# POWER.net
KiCad netlist of a schematic drawn in Altium Designer
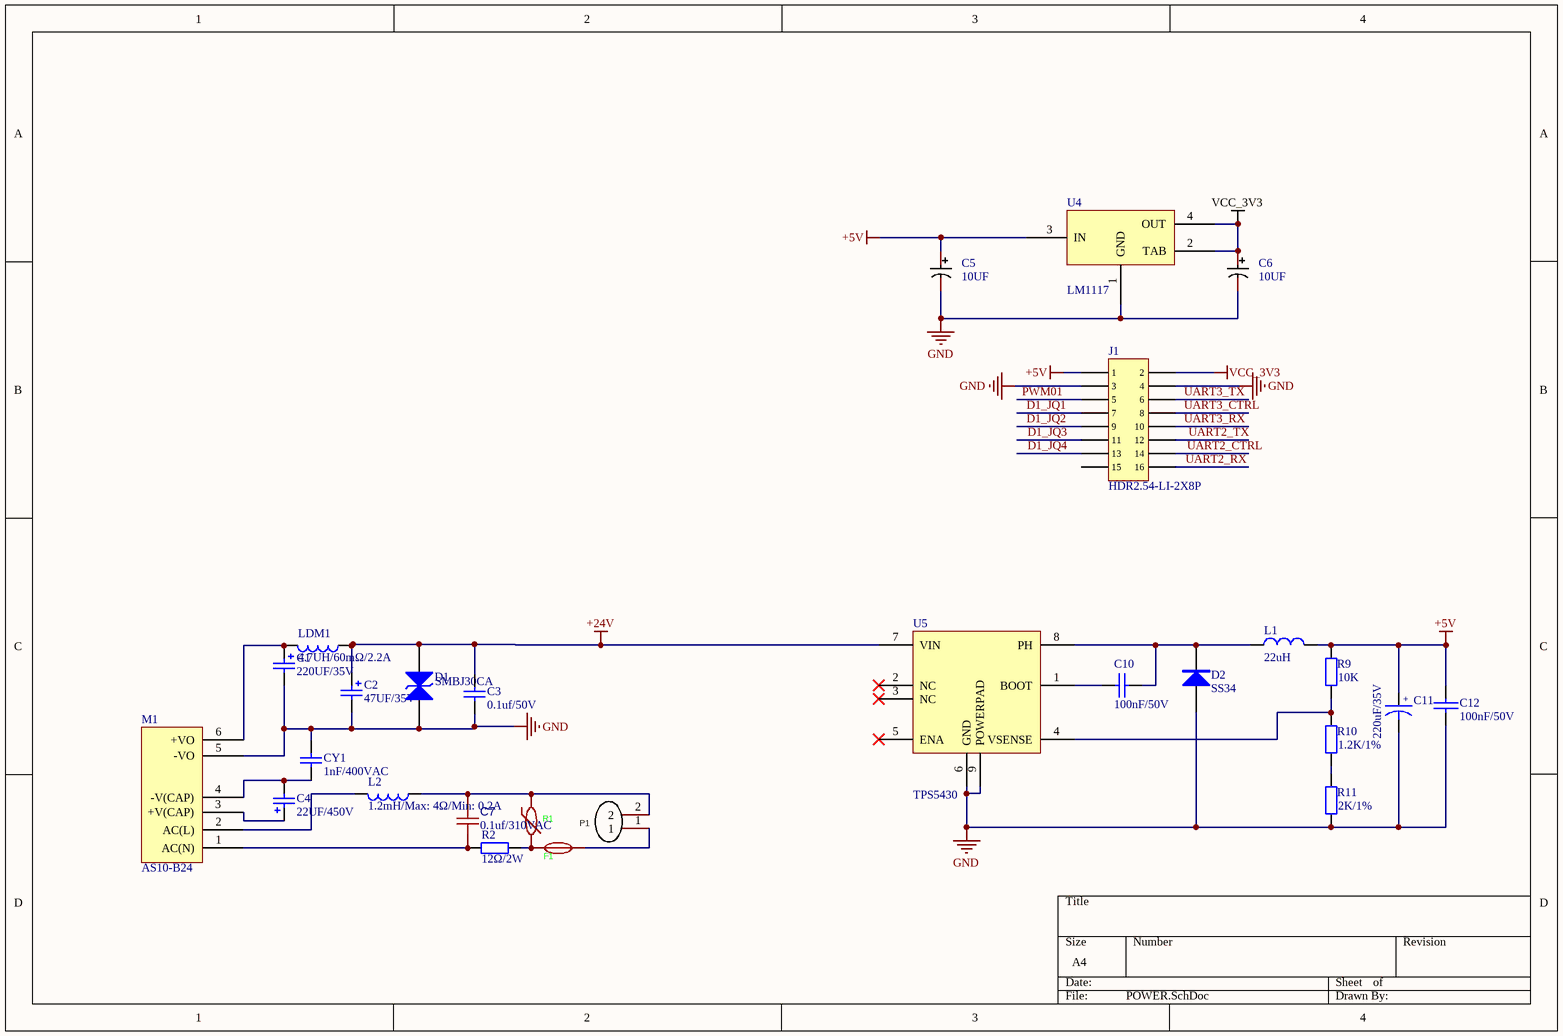
[diagram p0: POWER.SchDoc]

(export (version "E")
  (design (tool "Eeschema 10.0.6"))
  (components
    (comp (ref "C1")
      (value "220UF/35V")
      (footprint "CAP-TH_BD8.0-P3.50-D0.6-FD")
      (description "铝电解电容")
      (libsource (lib "电容") (part "CM-E 10uf 20% 25V"))
    )
    (comp (ref "C2")
      (value "47UF/35V")
      (footprint "CAP-TH_BD6.3-P2.50-D1.0-FD")
      (description "铝电解电容")
      (libsource (lib "电容") (part "CM-E 10uf 20% 25V"))
    )
    (comp (ref "C3")
      (value "0.1uf/50V")
      (footprint "C-0603")
      (description "贴片电容")
      (libsource (lib "电容") (part "0603' 100pF 5% 50V NP0 车规"))
    )
    (comp (ref "C4")
      (value "22UF/450V")
      (footprint "CAP-TH_BD12.5-P5.00-D0.6-FD")
      (description "铝电解电容")
      (libsource (lib "电容") (part "CM-E 10uf 20% 25V"))
    )
    (comp (ref "C5")
      (value "10UF")
      (footprint "CAP-TH_BD5.0-P2.00-D0.8-FD")
      (fields
        (field (name "MANUFACTURER") "CapXon(丰宾)")
        (field (name "MANUFACTURER PART") "KF470M050E110A")
        (field (name "TOLERANCE") "±20%")
      )
      (libsource (lib "altium-import") (part "root_3_KF470M050E110A_"))
    )
    (comp (ref "C6")
      (value "10UF")
      (footprint "CAP-TH_BD5.0-P2.00-D0.8-FD")
      (fields
        (field (name "MANUFACTURER") "CapXon(丰宾)")
        (field (name "MANUFACTURER PART") "KF470M050E110A")
        (field (name "TOLERANCE") "±20%")
      )
      (libsource (lib "altium-import") (part "root_3_KF470M050E110A_"))
    )
    (comp (ref "C7")
      (value "0.1uf/310VAC")
      (footprint "CAP-TH_L18.0-W6.0-P15.00-D0.8")
      (libsource (lib "altium-import") (part "root_1_PX104K2C1504_"))
    )
    (comp (ref "C10")
      (value "100nF/50V")
      (footprint "C-0805")
      (description "电容")
      (libsource (lib "泰开常用器件") (part "C普通电容"))
    )
    (comp (ref "C11")
      (value "220uF/35V")
      (footprint "CAP-TH_BD8.0-P3.50-D0.6-FD")
      (description "电解电容")
      (libsource (lib "常用器件") (part "C电解电容"))
    )
    (comp (ref "C12")
      (value "100nF/50V")
      (footprint "C-0805")
      (description "电容")
      (libsource (lib "泰开常用器件") (part "C普通电容"))
    )
    (comp (ref "CY1")
      (value "1nF/400VAC")
      (footprint "CAP-TH_L7.5-W4.5-P10.00-D0.6")
      (description "贴片电容")
      (libsource (lib "电容") (part "0603' 100pF 5% 50V NP0 车规"))
    )
    (comp (ref "D1")
      (value "SMBJ30CA")
      (footprint "DO-214AA")
      (description "TVS二极管")
      (libsource (lib "二极管") (part "DO-214AA' SMBJ30CA"))
    )
    (comp (ref "D2") (value "SS34") (footprint "DO-214AC") (libsource (lib "泰开常用器件") (part "DIODE")))
    (comp (ref "F1")
      (value "SCF2A")
      (footprint "FUSE-SMD_L6.1-W2.6")
      (description "2A/300V")
      (fields (field (name "MANUFACTURER") "TLC(竞沃)"))
      (libsource (lib "altium-import") (part "root_2_SCF2A_"))
    )
    (comp (ref "J1")
      (value "HDR2.54-LI-2X8P")
      (footprint "IDC-TH_16P-P2.54_BOOMELE-2X8P")
      (description "直插立式双排针")
      (libsource (lib "排针排母") (part "HDR2.54-LI-2X8P"))
    )
    (comp (ref "L1")
      (value "22uH")
      (footprint "L-CD75-2")
      (description "功率电感")
      (libsource (lib "泰开常用器件") (part "L"))
    )
    (comp (ref "L2")
      (value "1.2mH/Max: 4Ω/Min: 0.2A")
      (footprint "SRR1005-122K")
      (description "贴片电感（SRR1005-122K）")
      (libsource (lib "电感") (part "1206' 100uH 10%"))
    )
    (comp (ref "LDM1")
      (value "4.7UH/60mΩ/2.2A")
      (footprint "L-NR5020")
      (description "贴片电感")
      (libsource (lib "电感") (part "1206' 100uH 10%"))
    )
    (comp (ref "M1") (value "AS10-B24") (footprint "AS05-B24") (libsource (lib "模块") (part "AS10-B24")))
    (comp (ref "P1")
      (value "WJ500V-5.08-2P")
      (footprint "KF128-2P DG128")
      (fields (field (name "MANUFACTURER") "KANGNEX(康奈克斯电气)"))
      (libsource (lib "泰开常用器件") (part "WJ500V-5.08-2P"))
    )
    (comp (ref "R1")
      (value "14D561K")
      (footprint "10D561K")
      (fields (field (name "MANUFACTURER") "VDR(嵩隆)") (field (name "MANUFACTURER PART") "VDR-14D561K"))
      (libsource (lib "altium-import") (part "root_3_VDR-14D561K_"))
    )
    (comp (ref "R2")
      (value "12Ω/2W")
      (footprint "RES-TH_BD5.5-L15.0-P19.00-D0.8")
      (description "贴片电阻")
      (libsource (lib "电阻") (part "1206' 512"))
    )
    (comp (ref "R9")
      (value "10K")
      (footprint "R-0805")
      (description "电阻")
      (fields (field (name "PUBLISHER") "Altium Limited"))
      (libsource (lib "泰开常用器件") (part "RES"))
    )
    (comp (ref "R10")
      (value "1.2K/1%")
      (footprint "R-0805")
      (description "电阻")
      (fields (field (name "PUBLISHER") "Altium Limited"))
      (libsource (lib "泰开常用器件") (part "RES"))
    )
    (comp (ref "R11")
      (value "2K/1%")
      (footprint "R-0805")
      (description "电阻")
      (fields (field (name "PUBLISHER") "Altium Limited"))
      (libsource (lib "泰开常用器件") (part "RES"))
    )
    (comp (ref "U4")
      (value "LM1117")
      (footprint "SOT-223-3_L6.5-W3.4-P2.30-LS7.0-BR")
      (libsource (lib "泰开常用器件") (part "LM1117"))
    )
    (comp (ref "U5") (value "TPS5430") (footprint "ESOP-8") (libsource (lib "泰开常用器件") (part "TPS5430")))
  )
  (nets
    (net (code "1") (name "+5V") (class "Default")
      (node (ref "C11") (pin "1") (pinfunction "1_1") (pintype "passive"))
      (node (ref "C12") (pin "2") (pinfunction "2_2") (pintype "passive"))
      (node (ref "C5") (pin "1") (pinfunction "1_1") (pintype "passive"))
      (node (ref "J1") (pin "1") (pinfunction "1_1") (pintype "passive"))
      (node (ref "L1") (pin "2") (pinfunction "2_2") (pintype "passive"))
      (node (ref "R9") (pin "2") (pinfunction "2_2") (pintype "passive"))
      (node (ref "U4") (pin "3") (pinfunction "IN_3") (pintype "passive"))
    )
    (net (code "2") (name "+24V") (class "Default")
      (node (ref "C2") (pin "1") (pinfunction "1_1") (pintype "passive"))
      (node (ref "C3") (pin "2") (pinfunction "2_2") (pintype "passive"))
      (node (ref "D1") (pin "1") (pinfunction "1_1") (pintype "passive"))
      (node (ref "LDM1") (pin "1") (pinfunction "1_1") (pintype "passive"))
      (node (ref "U5") (pin "7") (pinfunction "VIN_7") (pintype "passive"))
    )
    (net (code "3") (name "/D1_JQ1") (class "Default")
      (node (ref "J1") (pin "7") (pinfunction "7_7") (pintype "passive"))
    )
    (net (code "4") (name "/D1_JQ2") (class "Default")
      (node (ref "J1") (pin "9") (pinfunction "9_9") (pintype "passive"))
    )
    (net (code "5") (name "/D1_JQ3") (class "Default")
      (node (ref "J1") (pin "11") (pinfunction "11_11") (pintype "passive"))
    )
    (net (code "6") (name "/D1_JQ4") (class "Default")
      (node (ref "J1") (pin "13") (pinfunction "13_13") (pintype "passive"))
    )
    (net (code "7") (name "/PWM01") (class "Default")
      (node (ref "J1") (pin "5") (pinfunction "5_5") (pintype "passive"))
    )
    (net (code "8") (name "/UART2_CTRL") (class "Default")
      (node (ref "J1") (pin "14") (pinfunction "14_14") (pintype "passive"))
    )
    (net (code "9") (name "/UART2_RX") (class "Default")
      (node (ref "J1") (pin "16") (pinfunction "16_16") (pintype "passive"))
    )
    (net (code "10") (name "/UART2_TX") (class "Default")
      (node (ref "J1") (pin "12") (pinfunction "12_12") (pintype "passive"))
    )
    (net (code "11") (name "/UART3_CTRL") (class "Default")
      (node (ref "J1") (pin "8") (pinfunction "8_8") (pintype "passive"))
    )
    (net (code "12") (name "/UART3_RX") (class "Default")
      (node (ref "J1") (pin "10") (pinfunction "10_10") (pintype "passive"))
    )
    (net (code "13") (name "/UART3_TX") (class "Default")
      (node (ref "J1") (pin "6") (pinfunction "6_6") (pintype "passive"))
    )
    (net (code "14") (name "GND") (class "Default")
      (node (ref "C1") (pin "2") (pinfunction "2_2") (pintype "passive"))
      (node (ref "C11") (pin "2") (pinfunction "2_2") (pintype "passive"))
      (node (ref "C12") (pin "1") (pinfunction "1_1") (pintype "passive"))
      (node (ref "C2") (pin "2") (pinfunction "2_2") (pintype "passive"))
      (node (ref "C3") (pin "1") (pinfunction "1_1") (pintype "passive"))
      (node (ref "C5") (pin "2") (pinfunction "2_2") (pintype "passive"))
      (node (ref "C6") (pin "2") (pinfunction "2_2") (pintype "passive"))
      (node (ref "CY1") (pin "2") (pinfunction "2_2") (pintype "passive"))
      (node (ref "D1") (pin "2") (pinfunction "2_2") (pintype "passive"))
      (node (ref "D2") (pin "1") (pinfunction "A_1") (pintype "passive"))
      (node (ref "J1") (pin "3") (pinfunction "3_3") (pintype "passive"))
      (node (ref "J1") (pin "4") (pinfunction "4_4") (pintype "passive"))
      (node (ref "M1") (pin "5") (pinfunction "-VO_5") (pintype "passive"))
      (node (ref "R11") (pin "1") (pinfunction "1_1") (pintype "passive"))
      (node (ref "U4") (pin "1") (pinfunction "GND_1") (pintype "passive"))
      (node (ref "U5") (pin "6") (pinfunction "GND_6") (pintype "passive"))
      (node (ref "U5") (pin "9") (pinfunction "POWERPAD_9") (pintype "passive"))
    )
    (net (code "15") (name "Net-(C7-Pad2)") (class "Default")
      (node (ref "C7") (pin "2") (pinfunction "2_2") (pintype "passive"))
      (node (ref "L2") (pin "1") (pinfunction "1_1") (pintype "passive"))
      (node (ref "P1") (pin "2") (pinfunction "2_2") (pintype "passive"))
      (node (ref "R1") (pin "1") (pinfunction "1_1") (pintype "passive"))
    )
    (net (code "16") (name "Net-(D2-K)") (class "Default")
      (node (ref "C10") (pin "1") (pinfunction "1_1") (pintype "passive"))
      (node (ref "D2") (pin "2") (pinfunction "K_2") (pintype "passive"))
      (node (ref "L1") (pin "1") (pinfunction "1_1") (pintype "passive"))
      (node (ref "U5") (pin "8") (pinfunction "PH_8") (pintype "passive"))
    )
    (net (code "17") (name "Net-(F1-Pad1)") (class "Default")
      (node (ref "F1") (pin "1") (pinfunction "1_1") (pintype "passive"))
      (node (ref "P1") (pin "1") (pinfunction "1_1") (pintype "passive"))
    )
    (net (code "18") (name "Net-(F1-Pad2)") (class "Default")
      (node (ref "F1") (pin "2") (pinfunction "2_2") (pintype "passive"))
      (node (ref "R1") (pin "2") (pinfunction "2_2") (pintype "passive"))
      (node (ref "R2") (pin "1") (pinfunction "1_1") (pintype "passive"))
    )
    (net (code "19") (name "Net-(M1-+V(CAP))") (class "Default")
      (node (ref "C4") (pin "1") (pinfunction "1_1") (pintype "passive"))
      (node (ref "M1") (pin "3") (pinfunction "+V(CAP)_3") (pintype "passive"))
    )
    (net (code "20") (name "Net-(M1-+VO)") (class "Default")
      (node (ref "C1") (pin "1") (pinfunction "1_1") (pintype "passive"))
      (node (ref "LDM1") (pin "2") (pinfunction "2_2") (pintype "passive"))
      (node (ref "M1") (pin "6") (pinfunction "+VO_6") (pintype "passive"))
    )
    (net (code "21") (name "Net-(M1--V(CAP))") (class "Default")
      (node (ref "C4") (pin "2") (pinfunction "2_2") (pintype "passive"))
      (node (ref "CY1") (pin "1") (pinfunction "1_1") (pintype "passive"))
      (node (ref "M1") (pin "4") (pinfunction "-V(CAP)_4") (pintype "passive"))
    )
    (net (code "22") (name "Net-(M1-AC(L))") (class "Default")
      (node (ref "L2") (pin "2") (pinfunction "2_2") (pintype "passive"))
      (node (ref "M1") (pin "2") (pinfunction "AC(L)_2") (pintype "passive"))
    )
    (net (code "23") (name "Net-(M1-AC(N))") (class "Default")
      (node (ref "C7") (pin "1") (pinfunction "1_1") (pintype "passive"))
      (node (ref "M1") (pin "1") (pinfunction "AC(N)_1") (pintype "passive"))
      (node (ref "R2") (pin "2") (pinfunction "2_2") (pintype "passive"))
    )
    (net (code "24") (name "Net-(R10-Pad1)") (class "Default")
      (node (ref "R10") (pin "1") (pinfunction "1_1") (pintype "passive"))
      (node (ref "R11") (pin "2") (pinfunction "2_2") (pintype "passive"))
    )
    (net (code "25") (name "Net-(U5-BOOT)") (class "Default")
      (node (ref "C10") (pin "2") (pinfunction "2_2") (pintype "passive"))
      (node (ref "U5") (pin "1") (pinfunction "BOOT_1") (pintype "passive"))
    )
    (net (code "26") (name "Net-(U5-VSENSE)") (class "Default")
      (node (ref "R10") (pin "2") (pinfunction "2_2") (pintype "passive"))
      (node (ref "R9") (pin "1") (pinfunction "1_1") (pintype "passive"))
      (node (ref "U5") (pin "4") (pinfunction "VSENSE_4") (pintype "passive"))
    )
    (net (code "27") (name "VCC_3V3") (class "Default")
      (node (ref "C6") (pin "1") (pinfunction "1_1") (pintype "passive"))
      (node (ref "J1") (pin "2") (pinfunction "2_2") (pintype "passive"))
      (node (ref "U4") (pin "2") (pinfunction "TAB_2") (pintype "passive"))
      (node (ref "U4") (pin "4") (pinfunction "OUT_4") (pintype "passive"))
    )
    (net (code "28") (name "unconnected-(J1-Pad15)") (class "Default")
      (node (ref "J1") (pin "15") (pinfunction "15_15") (pintype "passive"))
    )
    (net (code "29") (name "unconnected-(U5-ENA-Pad5)") (class "Default")
      (node (ref "U5") (pin "5") (pinfunction "ENA_5") (pintype "passive+no_connect"))
    )
    (net (code "30") (name "unconnected-(U5-NC-Pad2)") (class "Default")
      (node (ref "U5") (pin "2") (pinfunction "NC_2") (pintype "passive+no_connect"))
    )
    (net (code "31") (name "unconnected-(U5-NC-Pad3)") (class "Default")
      (node (ref "U5") (pin "3") (pinfunction "NC_3") (pintype "passive+no_connect"))
    )
  )
)
